# Edge_Touch_Module.net
KiCad netlist of a schematic drawn in EAGLE
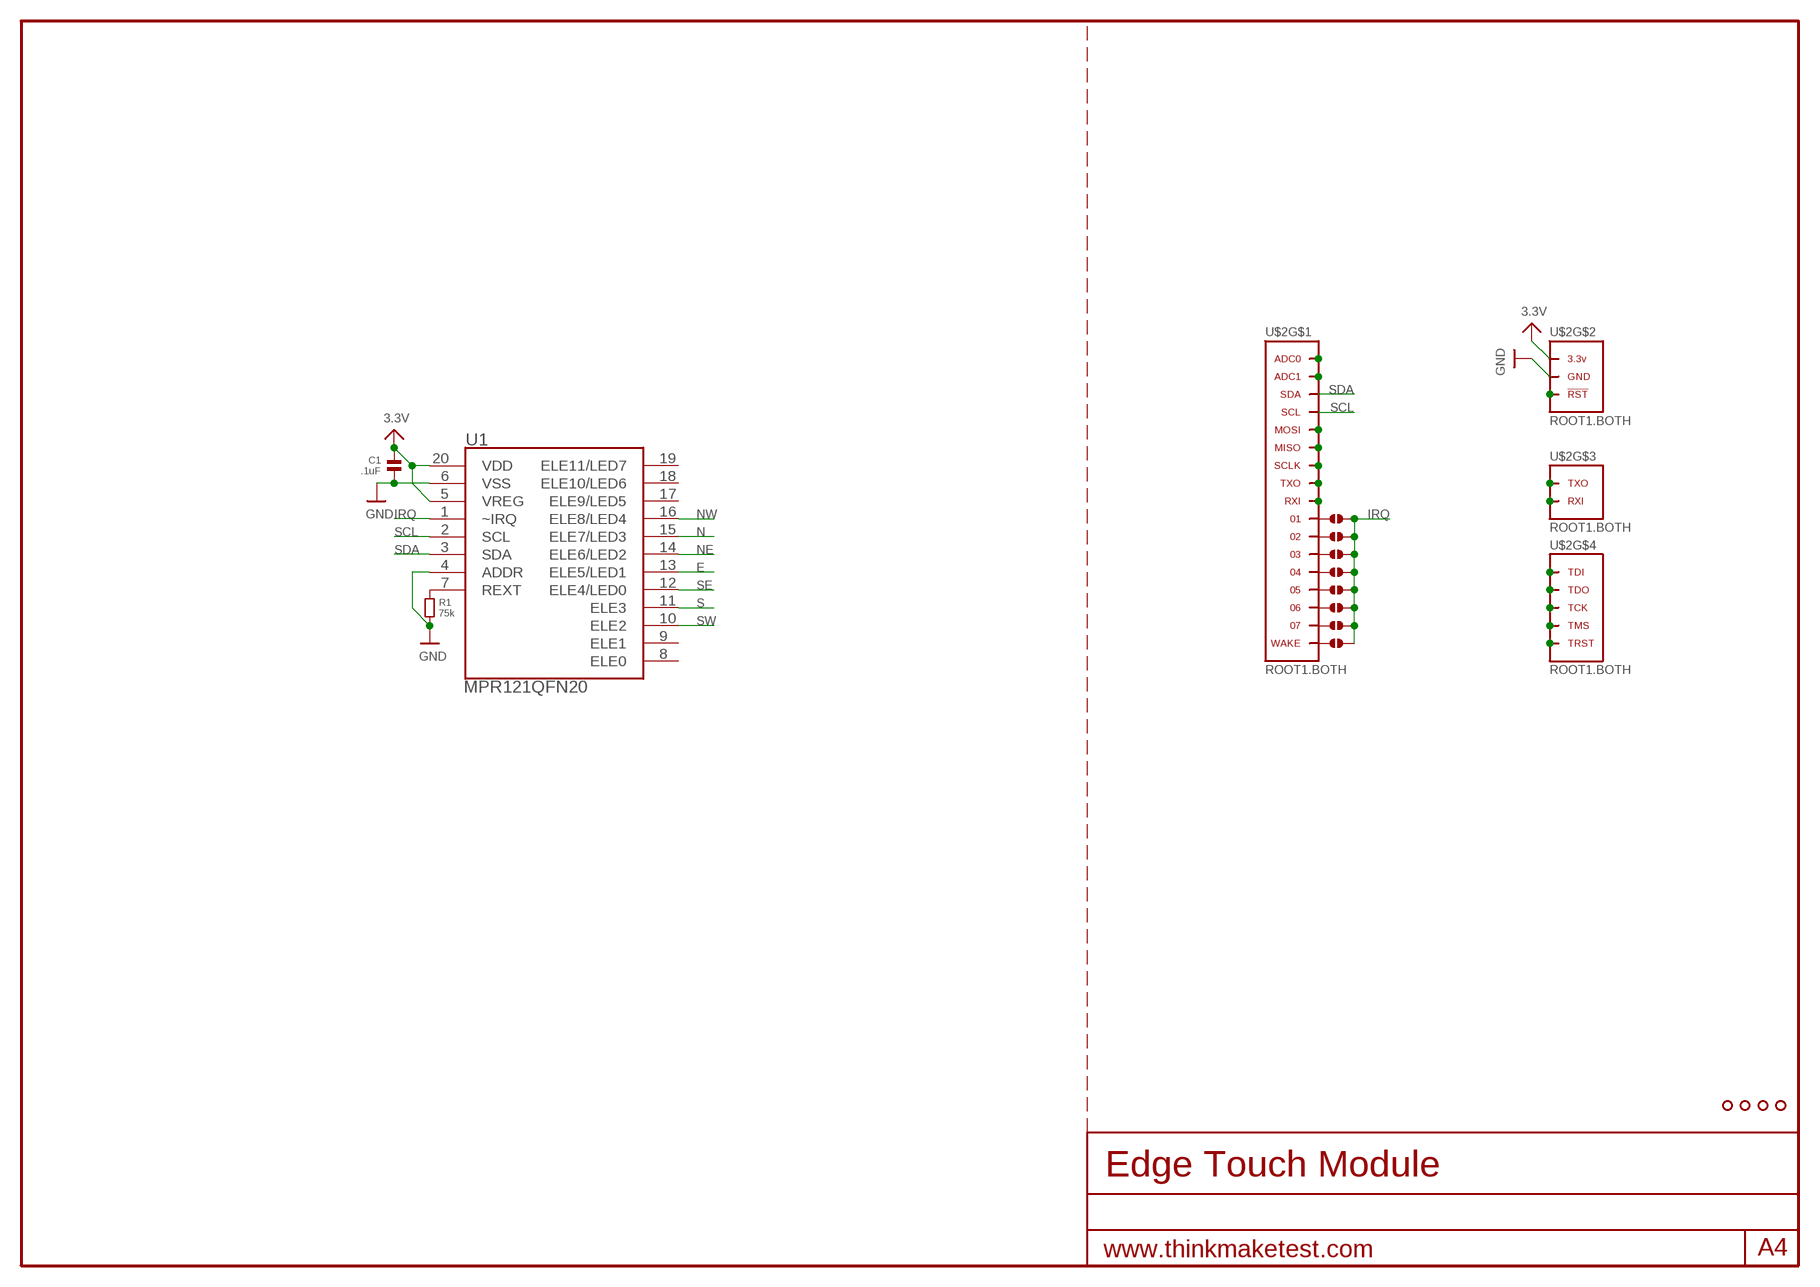
[diagram p0: schematic, sheet 1]

(export (version "E")
  (design (tool "Eeschema 10.0.6"))
  (components
    (comp (ref "1")
      (value "SOLDERJUMPER.2.SML")
      (footprint "eagle-import:2.SML")
      (libsource (lib "eagle-import") (part "SOLDERJUMPER.2.SML"))
    )
    (comp (ref "8")
      (value "SOLDERJUMPER.2.SML")
      (footprint "eagle-import:2.SML")
      (libsource (lib "eagle-import") (part "SOLDERJUMPER.2.SML"))
    )
    (comp (ref "C1")
      (value ".1uF")
      (footprint "eagle-import:0603")
      (libsource (lib "eagle-import") (part "CAPACITOR.0603"))
    )
    (comp (ref "J2")
      (value "SOLDERJUMPER.2.SML")
      (footprint "eagle-import:2.SML")
      (libsource (lib "eagle-import") (part "SOLDERJUMPER.2.SML"))
    )
    (comp (ref "J3")
      (value "SOLDERJUMPER.2.SML")
      (footprint "eagle-import:2.SML")
      (libsource (lib "eagle-import") (part "SOLDERJUMPER.2.SML"))
    )
    (comp (ref "J4")
      (value "SOLDERJUMPER.2.SML")
      (footprint "eagle-import:2.SML")
      (libsource (lib "eagle-import") (part "SOLDERJUMPER.2.SML"))
    )
    (comp (ref "J5")
      (value "SOLDERJUMPER.2.SML")
      (footprint "eagle-import:2.SML")
      (libsource (lib "eagle-import") (part "SOLDERJUMPER.2.SML"))
    )
    (comp (ref "J6")
      (value "SOLDERJUMPER.2.SML")
      (footprint "eagle-import:2.SML")
      (libsource (lib "eagle-import") (part "SOLDERJUMPER.2.SML"))
    )
    (comp (ref "J7")
      (value "SOLDERJUMPER.2.SML")
      (footprint "eagle-import:2.SML")
      (libsource (lib "eagle-import") (part "SOLDERJUMPER.2.SML"))
    )
    (comp (ref "R1")
      (value "75k")
      (footprint "eagle-import:0603")
      (libsource (lib "eagle-import") (part "RESISTOR.0603"))
    )
    (comp (ref "U$2")
      (value "ROOT1.BOTH")
      (footprint "eagle-import:ROOT1.BOTH")
      (libsource (lib "eagle-import") (part "ROOT1.BOTH"))
    )
    (comp (ref "U$3")
      (value "HOLE.#2")
      (footprint "eagle-import:#2")
      (libsource (lib "eagle-import") (part "HOLE.#2"))
    )
    (comp (ref "U$4")
      (value "HOLE.#2")
      (footprint "eagle-import:#2")
      (libsource (lib "eagle-import") (part "HOLE.#2"))
    )
    (comp (ref "U$9")
      (value "HOLE.#2")
      (footprint "eagle-import:#2")
      (libsource (lib "eagle-import") (part "HOLE.#2"))
    )
    (comp (ref "U$10")
      (value "HOLE.#2")
      (footprint "eagle-import:#2")
      (libsource (lib "eagle-import") (part "HOLE.#2"))
    )
    (comp (ref "U1")
      (value "MPR121QFN20")
      (footprint "eagle-import:QFN-20-0.4MM")
      (libsource (lib "eagle-import") (part "MPR121QFN20"))
    )
  )
  (nets
    (net (code "1") (name "/E") (class "Default")
      (node (ref "U1") (pin "13") (pinfunction "ELE5/LED1_13") (pintype "bidirectional"))
    )
    (net (code "2") (name "/IRQ") (class "Default")
      (node (ref "1") (pin "2") (pinfunction "2_2") (pintype "bidirectional"))
      (node (ref "8") (pin "2") (pinfunction "2_2") (pintype "bidirectional"))
      (node (ref "J2") (pin "2") (pinfunction "2_2") (pintype "bidirectional"))
      (node (ref "J3") (pin "2") (pinfunction "2_2") (pintype "bidirectional"))
      (node (ref "J4") (pin "2") (pinfunction "2_2") (pintype "bidirectional"))
      (node (ref "J5") (pin "2") (pinfunction "2_2") (pintype "bidirectional"))
      (node (ref "J6") (pin "2") (pinfunction "2_2") (pintype "bidirectional"))
      (node (ref "J7") (pin "2") (pinfunction "2_2") (pintype "bidirectional"))
      (node (ref "U1") (pin "1") (pinfunction "~{IRQ}_1") (pintype "bidirectional"))
    )
    (net (code "3") (name "/N") (class "Default")
      (node (ref "U1") (pin "15") (pinfunction "ELE7/LED3_15") (pintype "bidirectional"))
    )
    (net (code "4") (name "/NE") (class "Default")
      (node (ref "U1") (pin "14") (pinfunction "ELE6/LED2_14") (pintype "bidirectional"))
    )
    (net (code "5") (name "/NW") (class "Default")
      (node (ref "U1") (pin "16") (pinfunction "ELE8/LED4_16") (pintype "bidirectional"))
    )
    (net (code "6") (name "/S") (class "Default")
      (node (ref "U1") (pin "11") (pinfunction "ELE3_11") (pintype "bidirectional"))
    )
    (net (code "7") (name "/SCL") (class "Default")
      (node (ref "U$2") (pin "SCL") (pinfunction "SCL_SCL") (pintype "bidirectional"))
      (node (ref "U$2") (pin "SCL@1") (pinfunction "SCL_SCL@1") (pintype "bidirectional"))
      (node (ref "U$2") (pin "SCL@VIA") (pinfunction "SCL_SCL@VIA") (pintype "bidirectional"))
      (node (ref "U1") (pin "2") (pinfunction "SCL_2") (pintype "bidirectional"))
    )
    (net (code "8") (name "/SDA") (class "Default")
      (node (ref "U$2") (pin "SDA") (pinfunction "SDA_SDA") (pintype "bidirectional"))
      (node (ref "U$2") (pin "SDA@1") (pinfunction "SDA_SDA@1") (pintype "bidirectional"))
      (node (ref "U$2") (pin "SDA@VIA") (pinfunction "SDA_SDA@VIA") (pintype "bidirectional"))
      (node (ref "U1") (pin "3") (pinfunction "SDA_3") (pintype "bidirectional"))
    )
    (net (code "9") (name "/SE") (class "Default")
      (node (ref "U1") (pin "12") (pinfunction "ELE4/LED0_12") (pintype "bidirectional"))
    )
    (net (code "10") (name "/SW") (class "Default")
      (node (ref "U1") (pin "10") (pinfunction "ELE2_10") (pintype "bidirectional"))
    )
    (net (code "11") (name "3.3V") (class "Default")
      (node (ref "C1") (pin "1") (pinfunction "1_1") (pintype "bidirectional"))
      (node (ref "U$2") (pin "3.3V@1") (pinfunction "3.3V_3.3V@1") (pintype "bidirectional"))
      (node (ref "U$2") (pin "3.3V@10") (pinfunction "3.3V_3.3V@10") (pintype "bidirectional"))
      (node (ref "U$2") (pin "3.3V@11") (pinfunction "3.3V_3.3V@11") (pintype "bidirectional"))
      (node (ref "U$2") (pin "3.3V@12") (pinfunction "3.3V_3.3V@12") (pintype "bidirectional"))
      (node (ref "U$2") (pin "3.3V@13") (pinfunction "3.3V_3.3V@13") (pintype "bidirectional"))
      (node (ref "U$2") (pin "3.3V@14") (pinfunction "3.3V_3.3V@14") (pintype "bidirectional"))
      (node (ref "U$2") (pin "3.3V@15") (pinfunction "3.3V_3.3V@15") (pintype "bidirectional"))
      (node (ref "U$2") (pin "3.3V@16") (pinfunction "3.3V_3.3V@16") (pintype "bidirectional"))
      (node (ref "U$2") (pin "3.3V@17") (pinfunction "3.3V_3.3V@17") (pintype "bidirectional"))
      (node (ref "U$2") (pin "3.3V@18") (pinfunction "3.3V_3.3V@18") (pintype "bidirectional"))
      (node (ref "U$2") (pin "3.3V@19") (pinfunction "3.3V_3.3V@19") (pintype "bidirectional"))
      (node (ref "U$2") (pin "3.3V@2") (pinfunction "3.3V_3.3V@2") (pintype "bidirectional"))
      (node (ref "U$2") (pin "3.3V@20") (pinfunction "3.3V_3.3V@20") (pintype "bidirectional"))
      (node (ref "U$2") (pin "3.3V@21") (pinfunction "3.3V_3.3V@21") (pintype "bidirectional"))
      (node (ref "U$2") (pin "3.3V@22") (pinfunction "3.3V_3.3V@22") (pintype "bidirectional"))
      (node (ref "U$2") (pin "3.3V@23") (pinfunction "3.3V_3.3V@23") (pintype "bidirectional"))
      (node (ref "U$2") (pin "3.3V@24") (pinfunction "3.3V_3.3V@24") (pintype "bidirectional"))
      (node (ref "U$2") (pin "3.3V@3") (pinfunction "3.3V_3.3V@3") (pintype "bidirectional"))
      (node (ref "U$2") (pin "3.3V@4") (pinfunction "3.3V_3.3V@4") (pintype "bidirectional"))
      (node (ref "U$2") (pin "3.3V@5") (pinfunction "3.3V_3.3V@5") (pintype "bidirectional"))
      (node (ref "U$2") (pin "3.3V@6") (pinfunction "3.3V_3.3V@6") (pintype "bidirectional"))
      (node (ref "U$2") (pin "3.3V@7") (pinfunction "3.3V_3.3V@7") (pintype "bidirectional"))
      (node (ref "U$2") (pin "3.3V@8") (pinfunction "3.3V_3.3V@8") (pintype "bidirectional"))
      (node (ref "U$2") (pin "3.3V@9") (pinfunction "3.3V_3.3V@9") (pintype "bidirectional"))
      (node (ref "U$2") (pin "3.3V@VIA") (pinfunction "3.3V_3.3V@VIA") (pintype "bidirectional"))
      (node (ref "U1") (pin "20") (pinfunction "VDD_20") (pintype "bidirectional"))
      (node (ref "U1") (pin "5") (pinfunction "VREG_5") (pintype "bidirectional"))
    )
    (net (code "12") (name "GND") (class "Default")
      (node (ref "C1") (pin "2") (pinfunction "2_2") (pintype "bidirectional"))
      (node (ref "R1") (pin "2") (pinfunction "2_2") (pintype "bidirectional"))
      (node (ref "U$2") (pin "GND@1") (pinfunction "GND_GND@1") (pintype "bidirectional"))
      (node (ref "U$2") (pin "GND@10") (pinfunction "GND_GND@10") (pintype "bidirectional"))
      (node (ref "U$2") (pin "GND@11") (pinfunction "GND_GND@11") (pintype "bidirectional"))
      (node (ref "U$2") (pin "GND@12") (pinfunction "GND_GND@12") (pintype "bidirectional"))
      (node (ref "U$2") (pin "GND@13") (pinfunction "GND_GND@13") (pintype "bidirectional"))
      (node (ref "U$2") (pin "GND@14") (pinfunction "GND_GND@14") (pintype "bidirectional"))
      (node (ref "U$2") (pin "GND@15") (pinfunction "GND_GND@15") (pintype "bidirectional"))
      (node (ref "U$2") (pin "GND@16") (pinfunction "GND_GND@16") (pintype "bidirectional"))
      (node (ref "U$2") (pin "GND@17") (pinfunction "GND_GND@17") (pintype "bidirectional"))
      (node (ref "U$2") (pin "GND@18") (pinfunction "GND_GND@18") (pintype "bidirectional"))
      (node (ref "U$2") (pin "GND@19") (pinfunction "GND_GND@19") (pintype "bidirectional"))
      (node (ref "U$2") (pin "GND@2") (pinfunction "GND_GND@2") (pintype "bidirectional"))
      (node (ref "U$2") (pin "GND@20") (pinfunction "GND_GND@20") (pintype "bidirectional"))
      (node (ref "U$2") (pin "GND@21") (pinfunction "GND_GND@21") (pintype "bidirectional"))
      (node (ref "U$2") (pin "GND@22") (pinfunction "GND_GND@22") (pintype "bidirectional"))
      (node (ref "U$2") (pin "GND@23") (pinfunction "GND_GND@23") (pintype "bidirectional"))
      (node (ref "U$2") (pin "GND@24") (pinfunction "GND_GND@24") (pintype "bidirectional"))
      (node (ref "U$2") (pin "GND@25") (pinfunction "GND_GND@25") (pintype "bidirectional"))
      (node (ref "U$2") (pin "GND@26") (pinfunction "GND_GND@26") (pintype "bidirectional"))
      (node (ref "U$2") (pin "GND@3") (pinfunction "GND_GND@3") (pintype "bidirectional"))
      (node (ref "U$2") (pin "GND@4") (pinfunction "GND_GND@4") (pintype "bidirectional"))
      (node (ref "U$2") (pin "GND@5") (pinfunction "GND_GND@5") (pintype "bidirectional"))
      (node (ref "U$2") (pin "GND@6") (pinfunction "GND_GND@6") (pintype "bidirectional"))
      (node (ref "U$2") (pin "GND@7") (pinfunction "GND_GND@7") (pintype "bidirectional"))
      (node (ref "U$2") (pin "GND@8") (pinfunction "GND_GND@8") (pintype "bidirectional"))
      (node (ref "U$2") (pin "GND@9") (pinfunction "GND_GND@9") (pintype "bidirectional"))
      (node (ref "U$2") (pin "GND@VIA") (pinfunction "GND_GND@VIA") (pintype "bidirectional"))
      (node (ref "U1") (pin "4") (pinfunction "ADDR_4") (pintype "bidirectional"))
      (node (ref "U1") (pin "6") (pinfunction "VSS_6") (pintype "bidirectional"))
    )
    (net (code "13") (name "Net-(1-Pad1)") (class "Default")
      (node (ref "1") (pin "1") (pinfunction "1_1") (pintype "bidirectional"))
      (node (ref "U$2") (pin "01") (pinfunction "01_01") (pintype "bidirectional"))
      (node (ref "U$2") (pin "01@1") (pinfunction "01_01@1") (pintype "bidirectional"))
      (node (ref "U$2") (pin "01@VIA") (pinfunction "01_01@VIA") (pintype "bidirectional"))
    )
    (net (code "14") (name "Net-(8-Pad1)") (class "Default")
      (node (ref "8") (pin "1") (pinfunction "1_1") (pintype "bidirectional"))
      (node (ref "U$2") (pin "WAKE") (pinfunction "WAKE_WAKE") (pintype "bidirectional"))
      (node (ref "U$2") (pin "WAKE@1") (pinfunction "WAKE_WAKE@1") (pintype "bidirectional"))
      (node (ref "U$2") (pin "WAKE@VIA") (pinfunction "WAKE_WAKE@VIA") (pintype "bidirectional"))
    )
    (net (code "15") (name "Net-(J2-Pad1)") (class "Default")
      (node (ref "J2") (pin "1") (pinfunction "1_1") (pintype "bidirectional"))
      (node (ref "U$2") (pin "02") (pinfunction "02_02") (pintype "bidirectional"))
      (node (ref "U$2") (pin "02@1") (pinfunction "02_02@1") (pintype "bidirectional"))
      (node (ref "U$2") (pin "02@VIA") (pinfunction "02_02@VIA") (pintype "bidirectional"))
    )
    (net (code "16") (name "Net-(J3-Pad1)") (class "Default")
      (node (ref "J3") (pin "1") (pinfunction "1_1") (pintype "bidirectional"))
      (node (ref "U$2") (pin "03") (pinfunction "03_03") (pintype "bidirectional"))
      (node (ref "U$2") (pin "03@1") (pinfunction "03_03@1") (pintype "bidirectional"))
      (node (ref "U$2") (pin "03@VIA") (pinfunction "03_03@VIA") (pintype "bidirectional"))
    )
    (net (code "17") (name "Net-(J4-Pad1)") (class "Default")
      (node (ref "J4") (pin "1") (pinfunction "1_1") (pintype "bidirectional"))
      (node (ref "U$2") (pin "04") (pinfunction "04_04") (pintype "bidirectional"))
      (node (ref "U$2") (pin "04@1") (pinfunction "04_04@1") (pintype "bidirectional"))
      (node (ref "U$2") (pin "04@VIA") (pinfunction "04_04@VIA") (pintype "bidirectional"))
    )
    (net (code "18") (name "Net-(J5-Pad1)") (class "Default")
      (node (ref "J5") (pin "1") (pinfunction "1_1") (pintype "bidirectional"))
      (node (ref "U$2") (pin "05") (pinfunction "05_05") (pintype "bidirectional"))
      (node (ref "U$2") (pin "05@1") (pinfunction "05_05@1") (pintype "bidirectional"))
      (node (ref "U$2") (pin "05@VIA") (pinfunction "05_05@VIA") (pintype "bidirectional"))
    )
    (net (code "19") (name "Net-(J6-Pad1)") (class "Default")
      (node (ref "J6") (pin "1") (pinfunction "1_1") (pintype "bidirectional"))
      (node (ref "U$2") (pin "06") (pinfunction "06_06") (pintype "bidirectional"))
      (node (ref "U$2") (pin "06@1") (pinfunction "06_06@1") (pintype "bidirectional"))
      (node (ref "U$2") (pin "06@VIA") (pinfunction "06_06@VIA") (pintype "bidirectional"))
    )
    (net (code "20") (name "Net-(J7-Pad1)") (class "Default")
      (node (ref "J7") (pin "1") (pinfunction "1_1") (pintype "bidirectional"))
      (node (ref "U$2") (pin "07") (pinfunction "07_07") (pintype "bidirectional"))
      (node (ref "U$2") (pin "07@1") (pinfunction "07_07@1") (pintype "bidirectional"))
      (node (ref "U$2") (pin "07@VIA") (pinfunction "07_07@VIA") (pintype "bidirectional"))
    )
    (net (code "21") (name "Net-(U$2-PadADC0)") (class "Default")
      (node (ref "U$2") (pin "ADC0") (pinfunction "ADC0_ADC0") (pintype "bidirectional"))
      (node (ref "U$2") (pin "ADC0@1") (pinfunction "ADC0_ADC0@1") (pintype "bidirectional"))
      (node (ref "U$2") (pin "ADC0@VIA") (pinfunction "ADC0_ADC0@VIA") (pintype "bidirectional"))
    )
    (net (code "22") (name "Net-(U$2-PadADC1)") (class "Default")
      (node (ref "U$2") (pin "ADC1") (pinfunction "ADC1_ADC1") (pintype "bidirectional"))
      (node (ref "U$2") (pin "ADC1@1") (pinfunction "ADC1_ADC1@1") (pintype "bidirectional"))
      (node (ref "U$2") (pin "ADC1@VIA") (pinfunction "ADC1_ADC1@VIA") (pintype "bidirectional"))
    )
    (net (code "23") (name "Net-(U$2-PadMISO)") (class "Default")
      (node (ref "U$2") (pin "MISO") (pinfunction "MISO_MISO") (pintype "bidirectional"))
      (node (ref "U$2") (pin "MISO@1") (pinfunction "MISO_MISO@1") (pintype "bidirectional"))
      (node (ref "U$2") (pin "MISO@VIA") (pinfunction "MISO_MISO@VIA") (pintype "bidirectional"))
    )
    (net (code "24") (name "Net-(U$2-PadMOSI)") (class "Default")
      (node (ref "U$2") (pin "MOSI") (pinfunction "MOSI_MOSI") (pintype "bidirectional"))
      (node (ref "U$2") (pin "MOSI@1") (pinfunction "MOSI_MOSI@1") (pintype "bidirectional"))
      (node (ref "U$2") (pin "MOSI@VIA") (pinfunction "MOSI_MOSI@VIA") (pintype "bidirectional"))
    )
    (net (code "25") (name "Net-(U$2-PadRXI)") (class "Default")
      (node (ref "U$2") (pin "RXI") (pinfunction "RXI_RXI") (pintype "bidirectional"))
      (node (ref "U$2") (pin "RXI@1") (pinfunction "RXI_RXI@1") (pintype "bidirectional"))
      (node (ref "U$2") (pin "RXI@VIA") (pinfunction "RXI_RXI@VIA") (pintype "bidirectional"))
    )
    (net (code "26") (name "Net-(U$2-PadSCLK)") (class "Default")
      (node (ref "U$2") (pin "SCLK") (pinfunction "SCLK_SCLK") (pintype "bidirectional"))
      (node (ref "U$2") (pin "SCLK@1") (pinfunction "SCLK_SCLK@1") (pintype "bidirectional"))
      (node (ref "U$2") (pin "SCLK@VIA") (pinfunction "SCLK_SCLK@VIA") (pintype "bidirectional"))
    )
    (net (code "27") (name "Net-(U$2-PadTCK)") (class "Default")
      (node (ref "U$2") (pin "TCK") (pinfunction "TCK_TCK") (pintype "bidirectional"))
      (node (ref "U$2") (pin "TCK@1") (pinfunction "TCK_TCK@1") (pintype "bidirectional"))
      (node (ref "U$2") (pin "TCK@VIA") (pinfunction "TCK_TCK@VIA") (pintype "bidirectional"))
    )
    (net (code "28") (name "Net-(U$2-PadTDI)") (class "Default")
      (node (ref "U$2") (pin "TDI") (pinfunction "TDI_TDI") (pintype "bidirectional"))
      (node (ref "U$2") (pin "TDI@1") (pinfunction "TDI_TDI@1") (pintype "bidirectional"))
      (node (ref "U$2") (pin "TDI@VIA") (pinfunction "TDI_TDI@VIA") (pintype "bidirectional"))
    )
    (net (code "29") (name "Net-(U$2-PadTDO)") (class "Default")
      (node (ref "U$2") (pin "TDO") (pinfunction "TDO_TDO") (pintype "bidirectional"))
      (node (ref "U$2") (pin "TDO@1") (pinfunction "TDO_TDO@1") (pintype "bidirectional"))
      (node (ref "U$2") (pin "TDO@VIA") (pinfunction "TDO_TDO@VIA") (pintype "bidirectional"))
    )
    (net (code "30") (name "Net-(U$2-PadTMS)") (class "Default")
      (node (ref "U$2") (pin "TMS") (pinfunction "TMS_TMS") (pintype "bidirectional"))
      (node (ref "U$2") (pin "TMS@1") (pinfunction "TMS_TMS@1") (pintype "bidirectional"))
      (node (ref "U$2") (pin "TMS@VIA") (pinfunction "TMS_TMS@VIA") (pintype "bidirectional"))
    )
    (net (code "31") (name "Net-(U$2-PadTRST)") (class "Default")
      (node (ref "U$2") (pin "TRST") (pinfunction "TRST_TRST") (pintype "bidirectional"))
      (node (ref "U$2") (pin "TRST@1") (pinfunction "TRST_TRST@1") (pintype "bidirectional"))
      (node (ref "U$2") (pin "TRST@VIA") (pinfunction "TRST_TRST@VIA") (pintype "bidirectional"))
    )
    (net (code "32") (name "Net-(U$2-PadTXO)") (class "Default")
      (node (ref "U$2") (pin "TXO") (pinfunction "TXO_TXO") (pintype "bidirectional"))
      (node (ref "U$2") (pin "TXO@1") (pinfunction "TXO_TXO@1") (pintype "bidirectional"))
      (node (ref "U$2") (pin "TXO@VIA") (pinfunction "TXO_TXO@VIA") (pintype "bidirectional"))
    )
    (net (code "33") (name "Net-(U$2B-~{RST}-PadRST)") (class "Default")
      (node (ref "U$2") (pin "RST") (pinfunction "~{RST}_RST") (pintype "bidirectional"))
      (node (ref "U$2") (pin "RST@1") (pinfunction "~{RST}_RST@1") (pintype "bidirectional"))
      (node (ref "U$2") (pin "RST@VIA") (pinfunction "~{RST}_RST@VIA") (pintype "bidirectional"))
    )
    (net (code "34") (name "Net-(U$2C-RXI-PadRXI.DBG)") (class "Default")
      (node (ref "U$2") (pin "RXI.DBG") (pinfunction "RXI_RXI.DBG") (pintype "bidirectional"))
      (node (ref "U$2") (pin "RXI.DBG@1") (pinfunction "RXI_RXI.DBG@1") (pintype "bidirectional"))
      (node (ref "U$2") (pin "RXI.DBG@VIA") (pinfunction "RXI_RXI.DBG@VIA") (pintype "bidirectional"))
    )
    (net (code "35") (name "Net-(U$2C-TXO-PadTXO.DBG)") (class "Default")
      (node (ref "U$2") (pin "TXO.DBG") (pinfunction "TXO_TXO.DBG") (pintype "bidirectional"))
      (node (ref "U$2") (pin "TXO.DBG@1") (pinfunction "TXO_TXO.DBG@1") (pintype "bidirectional"))
      (node (ref "U$2") (pin "TXO.DBG@VIA") (pinfunction "TXO_TXO.DBG@VIA") (pintype "bidirectional"))
    )
    (net (code "36") (name "Net-(U1-REXT)") (class "Default")
      (node (ref "R1") (pin "1") (pinfunction "1_1") (pintype "bidirectional"))
      (node (ref "U1") (pin "7") (pinfunction "REXT_7") (pintype "bidirectional"))
    )
    (net (code "37") (name "unconnected-(U1-ELE0-Pad8)") (class "Default")
      (node (ref "U1") (pin "8") (pinfunction "ELE0_8") (pintype "bidirectional"))
    )
    (net (code "38") (name "unconnected-(U1-ELE1-Pad9)") (class "Default")
      (node (ref "U1") (pin "9") (pinfunction "ELE1_9") (pintype "bidirectional"))
    )
    (net (code "39") (name "unconnected-(U1-ELE9{slash}LED5-Pad17)") (class "Default")
      (node (ref "U1") (pin "17") (pinfunction "ELE9/LED5_17") (pintype "bidirectional"))
    )
    (net (code "40") (name "unconnected-(U1-ELE10{slash}LED6-Pad18)") (class "Default")
      (node (ref "U1") (pin "18") (pinfunction "ELE10/LED6_18") (pintype "bidirectional"))
    )
    (net (code "41") (name "unconnected-(U1-ELE11{slash}LED7-Pad19)") (class "Default")
      (node (ref "U1") (pin "19") (pinfunction "ELE11/LED7_19") (pintype "bidirectional"))
    )
  )
)
